# FPGA_misc.net
KiCad netlist of a schematic drawn in Altium Designer
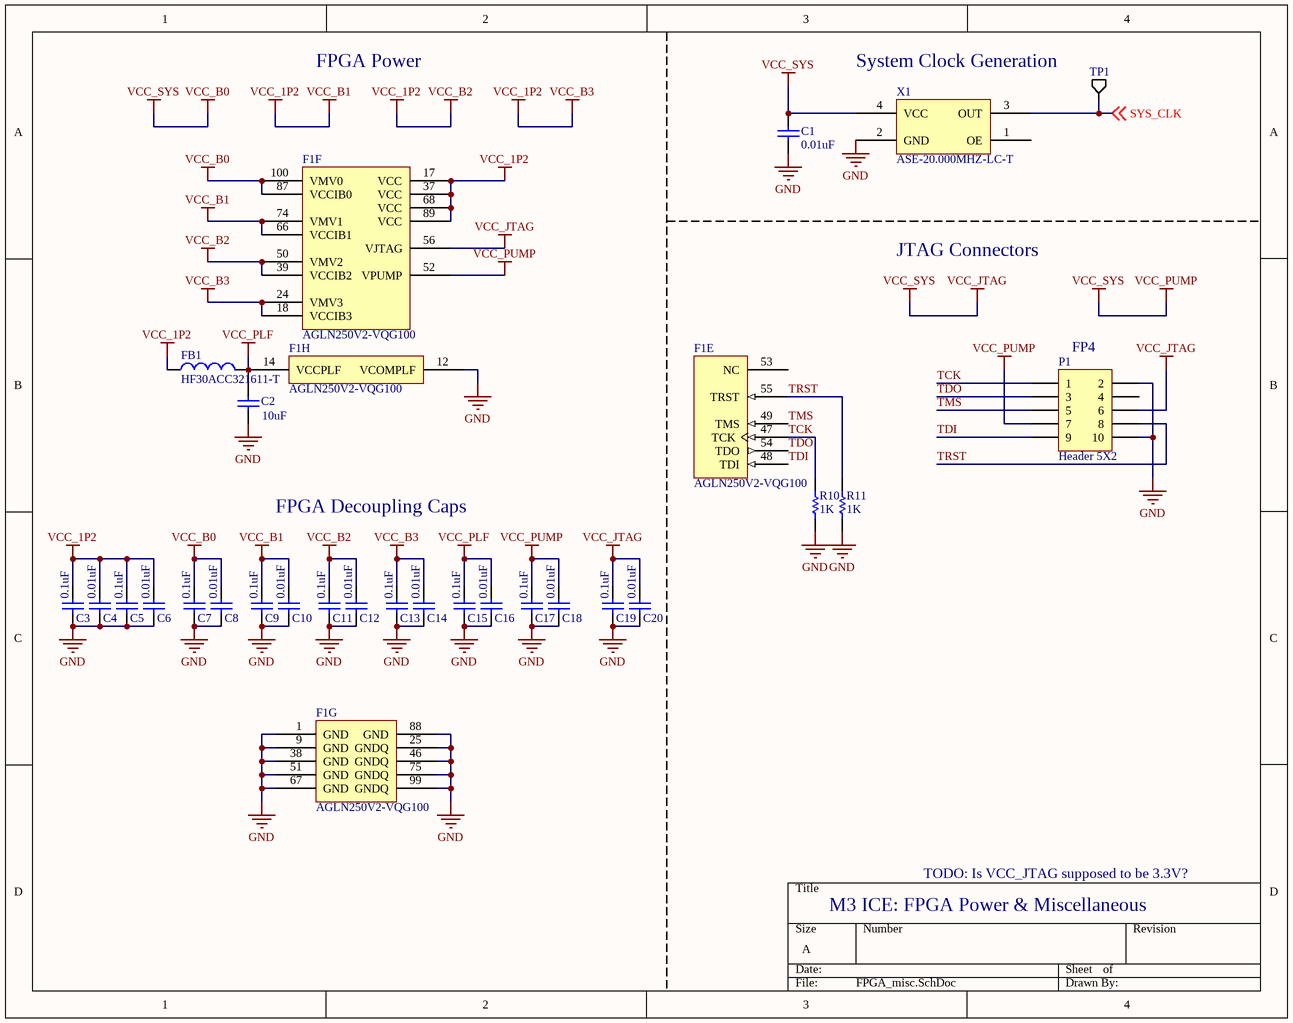
[diagram p0: FPGA_misc.SchDoc]

(export (version "E")
  (design (tool "Eeschema 10.0.6"))
  (components
    (comp (ref "C1")
      (value "0.01uF")
      (footprint "1608[0603]")
      (description "Capacitor (Semiconductor SIM Model)")
      (fields
        (field (name "DISTPARTNO") "445-1311-1-ND")
        (field (name "MANPARTNO") "C1608X7R1H103K")
        (field (name "PUBLISHER") "Altium Limited")
      )
      (libsource (lib "Miscellaneous Devices") (part "Cap Semi"))
    )
    (comp (ref "C2")
      (value "10uF")
      (footprint "0805")
      (description "Capacitor (Semiconductor SIM Model)")
      (fields
        (field (name "DISTPARTNO") "445-6857-1-ND")
        (field (name "MANPARTNO") "C2012X7R1A106K")
        (field (name "PUBLISHER") "Altium Limited")
      )
      (libsource (lib "M3") (part "Cap Chip"))
    )
    (comp (ref "C3")
      (value "0.1uF")
      (footprint "1608[0603]")
      (description "Capacitor (Semiconductor SIM Model)")
      (fields
        (field (name "DISTPARTNO") "1276-1005-1-ND")
        (field (name "MANPARTNO") "CL10B104KO8NNNC")
        (field (name "PUBLISHER") "Altium Limited")
      )
      (libsource (lib "Miscellaneous Devices") (part "Cap Semi"))
    )
    (comp (ref "C4")
      (value "0.01uF")
      (footprint "1608[0603]")
      (description "Capacitor (Semiconductor SIM Model)")
      (fields
        (field (name "DISTPARTNO") "445-1311-1-ND")
        (field (name "MANPARTNO") "C1608X7R1H103K")
        (field (name "PUBLISHER") "Altium Limited")
      )
      (libsource (lib "Miscellaneous Devices") (part "Cap Semi"))
    )
    (comp (ref "C5")
      (value "0.1uF")
      (footprint "1608[0603]")
      (description "Capacitor (Semiconductor SIM Model)")
      (fields
        (field (name "DISTPARTNO") "1276-1005-1-ND")
        (field (name "MANPARTNO") "CL10B104KO8NNNC")
        (field (name "PUBLISHER") "Altium Limited")
      )
      (libsource (lib "Miscellaneous Devices") (part "Cap Semi"))
    )
    (comp (ref "C6")
      (value "0.01uF")
      (footprint "1608[0603]")
      (description "Capacitor (Semiconductor SIM Model)")
      (fields
        (field (name "DISTPARTNO") "445-1311-1-ND")
        (field (name "MANPARTNO") "C1608X7R1H103K")
        (field (name "PUBLISHER") "Altium Limited")
      )
      (libsource (lib "Miscellaneous Devices") (part "Cap Semi"))
    )
    (comp (ref "C7")
      (value "0.1uF")
      (footprint "1608[0603]")
      (description "Capacitor (Semiconductor SIM Model)")
      (fields
        (field (name "DISTPARTNO") "1276-1005-1-ND")
        (field (name "MANPARTNO") "CL10B104KO8NNNC")
        (field (name "PUBLISHER") "Altium Limited")
      )
      (libsource (lib "Miscellaneous Devices") (part "Cap Semi"))
    )
    (comp (ref "C8")
      (value "0.01uF")
      (footprint "1608[0603]")
      (description "Capacitor (Semiconductor SIM Model)")
      (fields
        (field (name "DISTPARTNO") "445-1311-1-ND")
        (field (name "MANPARTNO") "C1608X7R1H103K")
        (field (name "PUBLISHER") "Altium Limited")
      )
      (libsource (lib "Miscellaneous Devices") (part "Cap Semi"))
    )
    (comp (ref "C9")
      (value "0.1uF")
      (footprint "1608[0603]")
      (description "Capacitor (Semiconductor SIM Model)")
      (fields
        (field (name "DISTPARTNO") "1276-1005-1-ND")
        (field (name "MANPARTNO") "CL10B104KO8NNNC")
        (field (name "PUBLISHER") "Altium Limited")
      )
      (libsource (lib "Miscellaneous Devices") (part "Cap Semi"))
    )
    (comp (ref "C10")
      (value "0.01uF")
      (footprint "1608[0603]")
      (description "Capacitor (Semiconductor SIM Model)")
      (fields
        (field (name "DISTPARTNO") "445-1311-1-ND")
        (field (name "MANPARTNO") "C1608X7R1H103K")
        (field (name "PUBLISHER") "Altium Limited")
      )
      (libsource (lib "Miscellaneous Devices") (part "Cap Semi"))
    )
    (comp (ref "C11")
      (value "0.1uF")
      (footprint "1608[0603]")
      (description "Capacitor (Semiconductor SIM Model)")
      (fields
        (field (name "DISTPARTNO") "1276-1005-1-ND")
        (field (name "MANPARTNO") "CL10B104KO8NNNC")
        (field (name "PUBLISHER") "Altium Limited")
      )
      (libsource (lib "Miscellaneous Devices") (part "Cap Semi"))
    )
    (comp (ref "C12")
      (value "0.01uF")
      (footprint "1608[0603]")
      (description "Capacitor (Semiconductor SIM Model)")
      (fields
        (field (name "DISTPARTNO") "445-1311-1-ND")
        (field (name "MANPARTNO") "C1608X7R1H103K")
        (field (name "PUBLISHER") "Altium Limited")
      )
      (libsource (lib "Miscellaneous Devices") (part "Cap Semi"))
    )
    (comp (ref "C13")
      (value "0.1uF")
      (footprint "1608[0603]")
      (description "Capacitor (Semiconductor SIM Model)")
      (fields
        (field (name "DISTPARTNO") "1276-1005-1-ND")
        (field (name "MANPARTNO") "CL10B104KO8NNNC")
        (field (name "PUBLISHER") "Altium Limited")
      )
      (libsource (lib "Miscellaneous Devices") (part "Cap Semi"))
    )
    (comp (ref "C14")
      (value "0.01uF")
      (footprint "1608[0603]")
      (description "Capacitor (Semiconductor SIM Model)")
      (fields
        (field (name "DISTPARTNO") "445-1311-1-ND")
        (field (name "MANPARTNO") "C1608X7R1H103K")
        (field (name "PUBLISHER") "Altium Limited")
      )
      (libsource (lib "Miscellaneous Devices") (part "Cap Semi"))
    )
    (comp (ref "C15")
      (value "0.1uF")
      (footprint "1608[0603]")
      (description "Capacitor (Semiconductor SIM Model)")
      (fields
        (field (name "DISTPARTNO") "1276-1005-1-ND")
        (field (name "MANPARTNO") "CL10B104KO8NNNC")
        (field (name "PUBLISHER") "Altium Limited")
      )
      (libsource (lib "Miscellaneous Devices") (part "Cap Semi"))
    )
    (comp (ref "C16")
      (value "0.01uF")
      (footprint "1608[0603]")
      (description "Capacitor (Semiconductor SIM Model)")
      (fields
        (field (name "DISTPARTNO") "445-1311-1-ND")
        (field (name "MANPARTNO") "C1608X7R1H103K")
        (field (name "PUBLISHER") "Altium Limited")
      )
      (libsource (lib "Miscellaneous Devices") (part "Cap Semi"))
    )
    (comp (ref "C17")
      (value "0.1uF")
      (footprint "1608[0603]")
      (description "Capacitor (Semiconductor SIM Model)")
      (fields
        (field (name "DISTPARTNO") "1276-1005-1-ND")
        (field (name "MANPARTNO") "CL10B104KO8NNNC")
        (field (name "PUBLISHER") "Altium Limited")
      )
      (libsource (lib "Miscellaneous Devices") (part "Cap Semi"))
    )
    (comp (ref "C18")
      (value "0.01uF")
      (footprint "1608[0603]")
      (description "Capacitor (Semiconductor SIM Model)")
      (fields
        (field (name "DISTPARTNO") "445-1311-1-ND")
        (field (name "MANPARTNO") "C1608X7R1H103K")
        (field (name "PUBLISHER") "Altium Limited")
      )
      (libsource (lib "Miscellaneous Devices") (part "Cap Semi"))
    )
    (comp (ref "C19")
      (value "0.1uF")
      (footprint "1608[0603]")
      (description "Capacitor (Semiconductor SIM Model)")
      (fields
        (field (name "DISTPARTNO") "1276-1005-1-ND")
        (field (name "MANPARTNO") "CL10B104KO8NNNC")
        (field (name "PUBLISHER") "Altium Limited")
      )
      (libsource (lib "Miscellaneous Devices") (part "Cap Semi"))
    )
    (comp (ref "C20")
      (value "0.01uF")
      (footprint "1608[0603]")
      (description "Capacitor (Semiconductor SIM Model)")
      (fields
        (field (name "DISTPARTNO") "445-1311-1-ND")
        (field (name "MANPARTNO") "C1608X7R1H103K")
        (field (name "PUBLISHER") "Altium Limited")
      )
      (libsource (lib "Miscellaneous Devices") (part "Cap Semi"))
    )
    (comp (ref "F1")
      (value "AGLN250V2-VQG100")
      (footprint "VQ100_N")
      (fields (field (name "DISTPARTNO") "1100-1134-ND") (field (name "PUBLISHER") "Altium Limited"))
      (libsource (lib "Actel IGLOO nano") (part "AGLN250V2-VQG100"))
    )
    (comp (ref "FB1")
      (value "HF30ACC321611-T")
      (footprint "Ferrite_Bead_3.2mm_1.6mm")
      (fields (field (name "DISTPARTNO") "445-6165-1-ND"))
      (libsource (lib "M3") (part "Ferrite Bead HF30ACC321611-T"))
    )
    (comp (ref "P1")
      (value "Header 5X2")
      (footprint "HDR2X5")
      (description "Header, 5-Pin, Dual row")
      (fields (field (name "PUBLISHER") "Altium Limited"))
      (libsource (lib "Miscellaneous Connectors") (part "Header 5X2"))
    )
    (comp (ref "R10")
      (value "1K")
      (footprint "0603")
      (description "Semiconductor Resistor")
      (fields
        (field (name "DISTPARTNO") "P1.0KGCT-ND")
        (field (name "MANPARTNO") "ERJ-3GEYJ102V")
        (field (name "PUBLISHER") "Altium Limited")
      )
      (libsource (lib "M3") (part "Res Chip"))
    )
    (comp (ref "R11")
      (value "1K")
      (footprint "0603")
      (description "Semiconductor Resistor")
      (fields
        (field (name "DISTPARTNO") "P1.0KGCT-ND")
        (field (name "MANPARTNO") "ERJ-3GEYJ102V")
        (field (name "PUBLISHER") "Altium Limited")
      )
      (libsource (lib "M3") (part "Res Chip"))
    )
    (comp (ref "TP1") (value "TP") (footprint "TP") (libsource (lib "M3") (part "TP")))
    (comp (ref "X1")
      (value "ASE-20.000MHZ-LC-T")
      (footprint "CRYSTAL_3.2mm_2.5mm")
      (fields (field (name "DISTPARTNO") "535-9565-1-ND"))
      (libsource (lib "M3") (part "ASE-20.000MHZ-LC-T"))
    )
  )
  (nets
    (net (code "1") (name "/TCK") (class "Default")
      (node (ref "F1") (pin "47") (pinfunction "TCK_47") (pintype "input"))
      (node (ref "P1") (pin "1") (pinfunction "1_1") (pintype "passive"))
      (node (ref "R10") (pin "1") (pinfunction "1_1") (pintype "passive"))
    )
    (net (code "2") (name "/TDI") (class "Default")
      (node (ref "F1") (pin "48") (pinfunction "TDI_48") (pintype "input"))
      (node (ref "P1") (pin "9") (pinfunction "9_9") (pintype "passive"))
    )
    (net (code "3") (name "/TDO") (class "Default")
      (node (ref "F1") (pin "54") (pinfunction "TDO_54") (pintype "output"))
      (node (ref "P1") (pin "3") (pinfunction "3_3") (pintype "passive"))
    )
    (net (code "4") (name "/TMS") (class "Default")
      (node (ref "F1") (pin "49") (pinfunction "TMS_49") (pintype "input"))
      (node (ref "P1") (pin "5") (pinfunction "5_5") (pintype "passive"))
    )
    (net (code "5") (name "/TRST") (class "Default")
      (node (ref "F1") (pin "55") (pinfunction "TRST_55") (pintype "input"))
      (node (ref "P1") (pin "8") (pinfunction "8_8") (pintype "passive"))
      (node (ref "R11") (pin "1") (pinfunction "1_1") (pintype "passive"))
    )
    (net (code "6") (name "GND") (class "Default")
      (node (ref "C1") (pin "1") (pinfunction "1_1") (pintype "passive"))
      (node (ref "C10") (pin "1") (pinfunction "1_1") (pintype "passive"))
      (node (ref "C11") (pin "1") (pinfunction "1_1") (pintype "passive"))
      (node (ref "C12") (pin "1") (pinfunction "1_1") (pintype "passive"))
      (node (ref "C13") (pin "1") (pinfunction "1_1") (pintype "passive"))
      (node (ref "C14") (pin "1") (pinfunction "1_1") (pintype "passive"))
      (node (ref "C15") (pin "1") (pinfunction "1_1") (pintype "passive"))
      (node (ref "C16") (pin "1") (pinfunction "1_1") (pintype "passive"))
      (node (ref "C17") (pin "1") (pinfunction "1_1") (pintype "passive"))
      (node (ref "C18") (pin "1") (pinfunction "1_1") (pintype "passive"))
      (node (ref "C19") (pin "1") (pinfunction "1_1") (pintype "passive"))
      (node (ref "C2") (pin "1") (pinfunction "1_1") (pintype "passive"))
      (node (ref "C20") (pin "1") (pinfunction "1_1") (pintype "passive"))
      (node (ref "C3") (pin "1") (pinfunction "1_1") (pintype "passive"))
      (node (ref "C4") (pin "1") (pinfunction "1_1") (pintype "passive"))
      (node (ref "C5") (pin "1") (pinfunction "1_1") (pintype "passive"))
      (node (ref "C6") (pin "1") (pinfunction "1_1") (pintype "passive"))
      (node (ref "C7") (pin "1") (pinfunction "1_1") (pintype "passive"))
      (node (ref "C8") (pin "1") (pinfunction "1_1") (pintype "passive"))
      (node (ref "C9") (pin "1") (pinfunction "1_1") (pintype "passive"))
      (node (ref "F1") (pin "1") (pinfunction "GND_1") (pintype "power_in"))
      (node (ref "F1") (pin "12") (pinfunction "VCOMPLF_12") (pintype "power_in"))
      (node (ref "F1") (pin "25") (pinfunction "GNDQ_25") (pintype "power_in"))
      (node (ref "F1") (pin "38") (pinfunction "GND_38") (pintype "power_in"))
      (node (ref "F1") (pin "46") (pinfunction "GNDQ_46") (pintype "power_in"))
      (node (ref "F1") (pin "51") (pinfunction "GND_51") (pintype "power_in"))
      (node (ref "F1") (pin "67") (pinfunction "GND_67") (pintype "power_in"))
      (node (ref "F1") (pin "75") (pinfunction "GNDQ_75") (pintype "power_in"))
      (node (ref "F1") (pin "88") (pinfunction "GND_88") (pintype "power_in"))
      (node (ref "F1") (pin "9") (pinfunction "GND_9") (pintype "power_in"))
      (node (ref "F1") (pin "99") (pinfunction "GNDQ_99") (pintype "power_in"))
      (node (ref "P1") (pin "10") (pinfunction "10_10") (pintype "passive"))
      (node (ref "P1") (pin "2") (pinfunction "2_2") (pintype "passive"))
      (node (ref "R10") (pin "2") (pinfunction "2_2") (pintype "passive"))
      (node (ref "R11") (pin "2") (pinfunction "2_2") (pintype "passive"))
      (node (ref "X1") (pin "2") (pinfunction "GND_2") (pintype "passive"))
    )
    (net (code "7") (name "SYS_CLK") (class "Default")
      (node (ref "TP1") (pin "1") (pinfunction "A_1") (pintype "passive"))
      (node (ref "X1") (pin "3") (pinfunction "OUT_3") (pintype "passive"))
    )
    (net (code "8") (name "VCC_1P2") (class "Default")
      (node (ref "C10") (pin "2") (pinfunction "2_2") (pintype "passive"))
      (node (ref "C11") (pin "2") (pinfunction "2_2") (pintype "passive"))
      (node (ref "C12") (pin "2") (pinfunction "2_2") (pintype "passive"))
      (node (ref "C13") (pin "2") (pinfunction "2_2") (pintype "passive"))
      (node (ref "C14") (pin "2") (pinfunction "2_2") (pintype "passive"))
      (node (ref "C3") (pin "2") (pinfunction "2_2") (pintype "passive"))
      (node (ref "C4") (pin "2") (pinfunction "2_2") (pintype "passive"))
      (node (ref "C5") (pin "2") (pinfunction "2_2") (pintype "passive"))
      (node (ref "C6") (pin "2") (pinfunction "2_2") (pintype "passive"))
      (node (ref "C9") (pin "2") (pinfunction "2_2") (pintype "passive"))
      (node (ref "F1") (pin "17") (pinfunction "VCC_17") (pintype "power_in"))
      (node (ref "F1") (pin "18") (pinfunction "VCCIB3_18") (pintype "power_in"))
      (node (ref "F1") (pin "24") (pinfunction "VMV3_24") (pintype "power_in"))
      (node (ref "F1") (pin "37") (pinfunction "VCC_37") (pintype "power_in"))
      (node (ref "F1") (pin "39") (pinfunction "VCCIB2_39") (pintype "power_in"))
      (node (ref "F1") (pin "50") (pinfunction "VMV2_50") (pintype "power_in"))
      (node (ref "F1") (pin "66") (pinfunction "VCCIB1_66") (pintype "power_in"))
      (node (ref "F1") (pin "68") (pinfunction "VCC_68") (pintype "power_in"))
      (node (ref "F1") (pin "74") (pinfunction "VMV1_74") (pintype "power_in"))
      (node (ref "F1") (pin "89") (pinfunction "VCC_89") (pintype "power_in"))
      (node (ref "FB1") (pin "1") (pinfunction "1_1") (pintype "passive"))
    )
    (net (code "9") (name "VCC_B0") (class "Default")
      (node (ref "C1") (pin "2") (pinfunction "2_2") (pintype "passive"))
      (node (ref "C17") (pin "2") (pinfunction "2_2") (pintype "passive"))
      (node (ref "C18") (pin "2") (pinfunction "2_2") (pintype "passive"))
      (node (ref "C19") (pin "2") (pinfunction "2_2") (pintype "passive"))
      (node (ref "C20") (pin "2") (pinfunction "2_2") (pintype "passive"))
      (node (ref "C7") (pin "2") (pinfunction "2_2") (pintype "passive"))
      (node (ref "C8") (pin "2") (pinfunction "2_2") (pintype "passive"))
      (node (ref "F1") (pin "100") (pinfunction "VMV0_100") (pintype "power_in"))
      (node (ref "F1") (pin "52") (pinfunction "VPUMP_52") (pintype "power_in"))
      (node (ref "F1") (pin "56") (pinfunction "VJTAG_56") (pintype "power_in"))
      (node (ref "F1") (pin "87") (pinfunction "VCCIB0_87") (pintype "power_in"))
      (node (ref "P1") (pin "6") (pinfunction "6_6") (pintype "passive"))
      (node (ref "P1") (pin "7") (pinfunction "7_7") (pintype "passive"))
      (node (ref "X1") (pin "4") (pinfunction "VCC_4") (pintype "passive"))
    )
    (net (code "10") (name "VCC_PLF") (class "Default")
      (node (ref "C15") (pin "2") (pinfunction "2_2") (pintype "passive"))
      (node (ref "C16") (pin "2") (pinfunction "2_2") (pintype "passive"))
      (node (ref "C2") (pin "2") (pinfunction "2_2") (pintype "passive"))
      (node (ref "F1") (pin "14") (pinfunction "VCCPLF_14") (pintype "power_in"))
      (node (ref "FB1") (pin "2") (pinfunction "2_2") (pintype "passive"))
    )
    (net (code "11") (name "unconnected-(F1E-NC-Pad53)") (class "Default")
      (node (ref "F1") (pin "53") (pinfunction "NC_53") (pintype "passive"))
    )
    (net (code "12") (name "unconnected-(P1-Pad4)") (class "Default")
      (node (ref "P1") (pin "4") (pinfunction "4_4") (pintype "passive"))
    )
    (net (code "13") (name "unconnected-(X1-OE-Pad1)") (class "Default")
      (node (ref "X1") (pin "1") (pinfunction "OE_1") (pintype "passive"))
    )
  )
)
